# MCU.net
KiCad netlist of a schematic drawn in Altium Designer
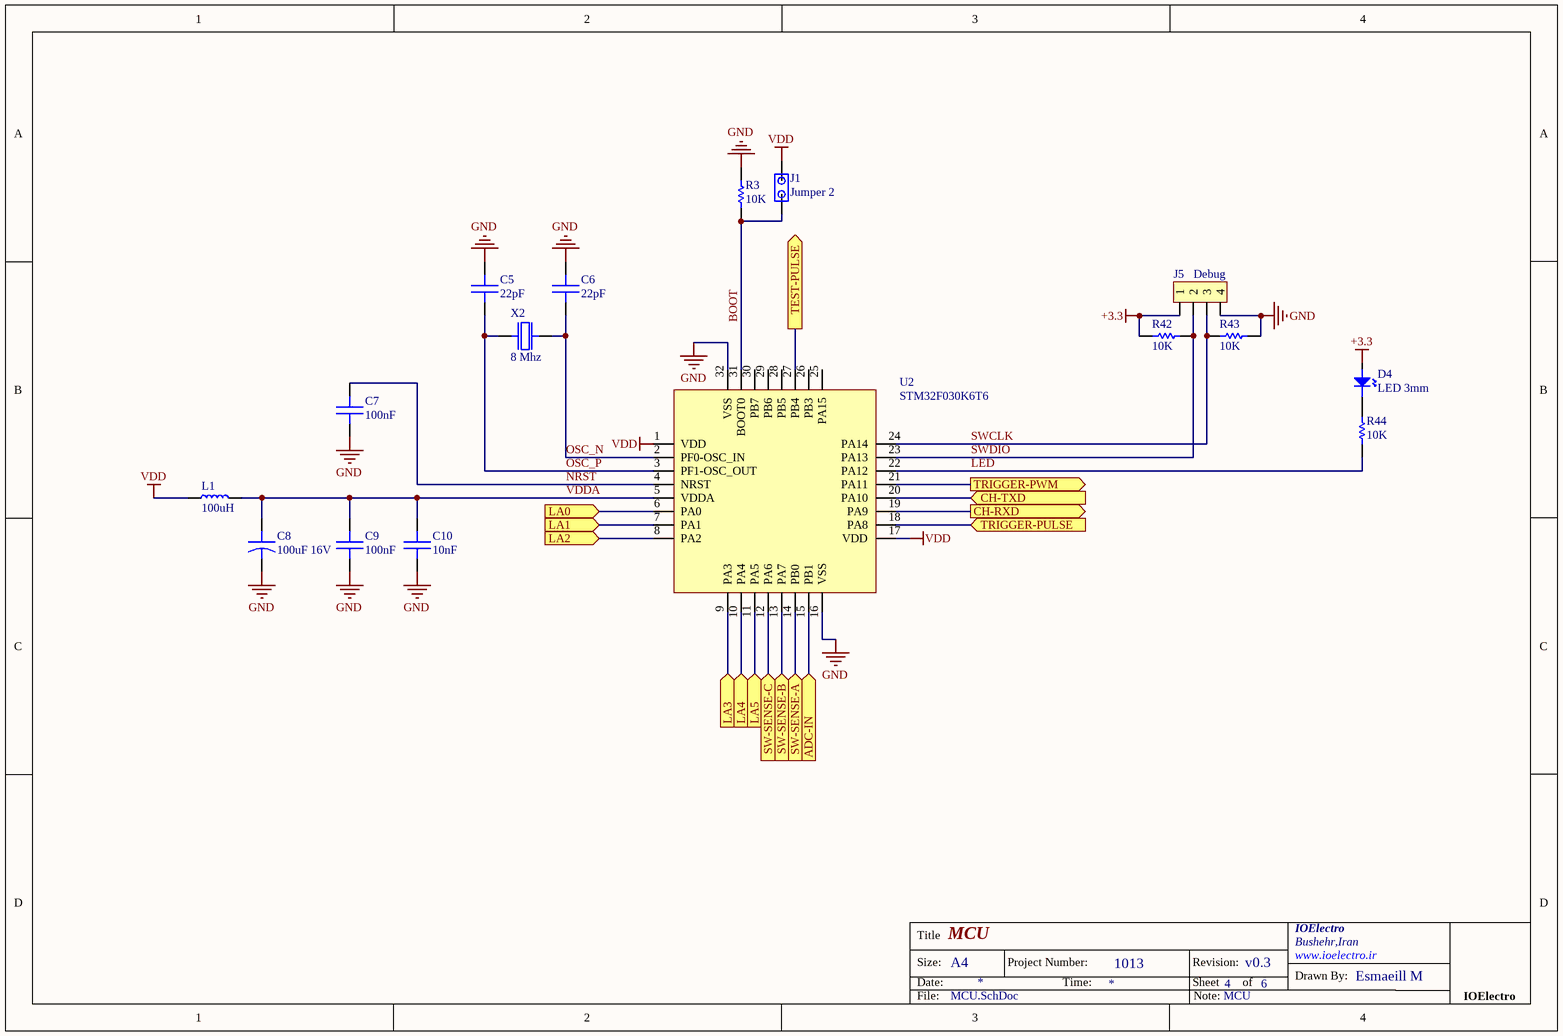
[diagram p0: MCU.SchDoc]

(export (version "E")
  (design (tool "Eeschema 10.0.6"))
  (components
    (comp (ref "C5")
      (value "22pF")
      (footprint "C-0805")
      (description "SMD 0805")
      (libsource (lib "IOElectro") (part "CAP"))
    )
    (comp (ref "C6")
      (value "22pF")
      (footprint "C-0805")
      (description "SMD 0805")
      (libsource (lib "IOElectro") (part "CAP"))
    )
    (comp (ref "C7")
      (value "100nF")
      (footprint "C-0805")
      (description "SMD 0805")
      (libsource (lib "IOElectro") (part "CAP"))
    )
    (comp (ref "C8")
      (value "100uF 16V")
      (footprint "C-EL_6.5x7x2.5mm")
      (description "CAPACITOR ELECTROLYTIC 6.3x7mm")
      (libsource (lib "IOElectro") (part "CAP-EL"))
    )
    (comp (ref "C9")
      (value "100nF")
      (footprint "C-0805")
      (description "SMD 0805")
      (libsource (lib "IOElectro") (part "CAP"))
    )
    (comp (ref "C10")
      (value "10nF")
      (footprint "C-0805")
      (description "SMD 0805")
      (libsource (lib "IOElectro") (part "CAP"))
    )
    (comp (ref "D4")
      (value "LED 3mm")
      (footprint "LED-3MM")
      (description "LED")
      (libsource (lib "IOElectro") (part "LED"))
    )
    (comp (ref "J1")
      (value "Jumper 2")
      (footprint "JAMPER-2-DIP_2.56mm")
      (description "2PIN DIP JAMPER 2.56mm")
      (libsource (lib "IOElectro") (part "JUMPER-2"))
    )
    (comp (ref "J5")
      (value "Debug")
      (footprint "PH-1X4")
      (description "PIN HEADER 1x4 2.56mm")
      (libsource (lib "Schlib") (part "PH-1X4"))
    )
    (comp (ref "L1")
      (value "100uH")
      (footprint "L-DIP_3x7mm_pin9mm")
      (description "Axial Lead Inductors(Coils)For Signal Line 100uH 165mA")
      (libsource (lib "IOElectro") (part "AL0307-101K-LF"))
    )
    (comp (ref "R3")
      (value "10K")
      (footprint "R-0805")
      (description "0805")
      (libsource (lib "IOElectro") (part "RES"))
    )
    (comp (ref "R42")
      (value "10K")
      (footprint "R-0805")
      (description "0805")
      (libsource (lib "IOElectro") (part "RES"))
    )
    (comp (ref "R43")
      (value "10K")
      (footprint "R-0805")
      (description "0805")
      (libsource (lib "IOElectro") (part "RES"))
    )
    (comp (ref "R44")
      (value "10K")
      (footprint "R-0805")
      (description "0805")
      (libsource (lib "IOElectro") (part "RES"))
    )
    (comp (ref "U2")
      (value "STM32F030K6T6")
      (footprint "LQFP-32")
      (fields (field (name "MANUFACTURER") "STMicroelectronics"))
      (libsource (lib "IOElectro") (part "STM32F030K6T6"))
    )
    (comp (ref "X2")
      (value "8 Mhz")
      (footprint "XTAL-DIP_Small")
      (description "Crystal oscillator")
      (libsource (lib "IOElectro") (part "XTAL"))
    )
  )
  (nets
    (net (code "1") (name "+3.3") (class "Default")
      (node (ref "D4") (pin "A") (pinfunction "A_A") (pintype "passive"))
      (node (ref "J5") (pin "1") (pinfunction "1_1") (pintype "passive"))
      (node (ref "R42") (pin "1") (pinfunction "1_1") (pintype "passive"))
    )
    (net (code "3") (name "/ADC-IN") (class "Default")
      (node (ref "U2") (pin "15") (pinfunction "PB1_15") (pintype "passive"))
    )
    (net (code "4") (name "/BOOT") (class "Default")
      (node (ref "J1") (pin "1") (pinfunction "1_1") (pintype "passive"))
      (node (ref "R3") (pin "1") (pinfunction "1_1") (pintype "passive"))
      (node (ref "U2") (pin "31") (pinfunction "BOOT0_31") (pintype "passive"))
    )
    (net (code "5") (name "/CH-RXD") (class "Default")
      (node (ref "U2") (pin "19") (pinfunction "PA9_19") (pintype "passive"))
    )
    (net (code "6") (name "/CH-TXD") (class "Default")
      (node (ref "U2") (pin "20") (pinfunction "PA10_20") (pintype "passive"))
    )
    (net (code "7") (name "/LA0") (class "Default")
      (node (ref "U2") (pin "6") (pinfunction "PA0_6") (pintype "passive"))
    )
    (net (code "8") (name "/LA1") (class "Default")
      (node (ref "U2") (pin "7") (pinfunction "PA1_7") (pintype "passive"))
    )
    (net (code "9") (name "/LA2") (class "Default")
      (node (ref "U2") (pin "8") (pinfunction "PA2_8") (pintype "passive"))
    )
    (net (code "10") (name "/LA3") (class "Default")
      (node (ref "U2") (pin "9") (pinfunction "PA3_9") (pintype "passive"))
    )
    (net (code "11") (name "/LA4") (class "Default")
      (node (ref "U2") (pin "10") (pinfunction "PA4_10") (pintype "passive"))
    )
    (net (code "12") (name "/LA5") (class "Default")
      (node (ref "U2") (pin "11") (pinfunction "PA5_11") (pintype "passive"))
    )
    (net (code "13") (name "/LED") (class "Default")
      (node (ref "R44") (pin "2") (pinfunction "2_2") (pintype "passive"))
      (node (ref "U2") (pin "22") (pinfunction "PA12_22") (pintype "passive"))
    )
    (net (code "14") (name "/NRST") (class "Default")
      (node (ref "C7") (pin "1") (pinfunction "1_1") (pintype "passive"))
      (node (ref "U2") (pin "4") (pinfunction "NRST_4") (pintype "passive"))
    )
    (net (code "15") (name "/OSC_N") (class "Default")
      (node (ref "C6") (pin "1") (pinfunction "1_1") (pintype "passive"))
      (node (ref "U2") (pin "2") (pinfunction "PF0-OSC_IN_2") (pintype "passive"))
      (node (ref "X2") (pin "2") (pinfunction "2_2") (pintype "passive"))
    )
    (net (code "16") (name "/OSC_P") (class "Default")
      (node (ref "C5") (pin "1") (pinfunction "1_1") (pintype "passive"))
      (node (ref "U2") (pin "3") (pinfunction "PF1-OSC_OUT_3") (pintype "passive"))
      (node (ref "X2") (pin "1") (pinfunction "1_1") (pintype "passive"))
    )
    (net (code "17") (name "/SW-SENSE-A") (class "Default")
      (node (ref "U2") (pin "14") (pinfunction "PB0_14") (pintype "passive"))
    )
    (net (code "18") (name "/SW-SENSE-B") (class "Default")
      (node (ref "U2") (pin "13") (pinfunction "PA7_13") (pintype "passive"))
    )
    (net (code "19") (name "/SW-SENSE-C") (class "Default")
      (node (ref "U2") (pin "12") (pinfunction "PA6_12") (pintype "passive"))
    )
    (net (code "20") (name "/SWCLK") (class "Default")
      (node (ref "J5") (pin "3") (pinfunction "3_3") (pintype "passive"))
      (node (ref "R43") (pin "1") (pinfunction "1_1") (pintype "passive"))
      (node (ref "U2") (pin "24") (pinfunction "PA14_24") (pintype "passive"))
    )
    (net (code "21") (name "/SWDIO") (class "Default")
      (node (ref "J5") (pin "2") (pinfunction "2_2") (pintype "passive"))
      (node (ref "R42") (pin "2") (pinfunction "2_2") (pintype "passive"))
      (node (ref "U2") (pin "23") (pinfunction "PA13_23") (pintype "passive"))
    )
    (net (code "22") (name "/TEST-PULSE") (class "Default")
      (node (ref "U2") (pin "27") (pinfunction "PB4_27") (pintype "passive"))
    )
    (net (code "23") (name "/TRIGGER-PULSE") (class "Default")
      (node (ref "U2") (pin "18") (pinfunction "PA8_18") (pintype "passive"))
    )
    (net (code "24") (name "/TRIGGER-PWM") (class "Default")
      (node (ref "U2") (pin "21") (pinfunction "PA11_21") (pintype "passive"))
    )
    (net (code "25") (name "/VDDA") (class "Default")
      (node (ref "C10") (pin "1") (pinfunction "1_1") (pintype "passive"))
      (node (ref "C8") (pin "A") (pinfunction "A_A") (pintype "passive"))
      (node (ref "C9") (pin "1") (pinfunction "1_1") (pintype "passive"))
      (node (ref "L1") (pin "2") (pinfunction "2_2") (pintype "passive"))
      (node (ref "U2") (pin "5") (pinfunction "VDDA_5") (pintype "passive"))
    )
    (net (code "26") (name "GND") (class "Default")
      (node (ref "C10") (pin "2") (pinfunction "2_2") (pintype "passive"))
      (node (ref "C5") (pin "2") (pinfunction "2_2") (pintype "passive"))
      (node (ref "C6") (pin "2") (pinfunction "2_2") (pintype "passive"))
      (node (ref "C7") (pin "2") (pinfunction "2_2") (pintype "passive"))
      (node (ref "C8") (pin "K") (pinfunction "K_K") (pintype "passive"))
      (node (ref "C9") (pin "2") (pinfunction "2_2") (pintype "passive"))
      (node (ref "J5") (pin "4") (pinfunction "4_4") (pintype "passive"))
      (node (ref "R3") (pin "2") (pinfunction "2_2") (pintype "passive"))
      (node (ref "R43") (pin "2") (pinfunction "2_2") (pintype "passive"))
      (node (ref "U2") (pin "16") (pinfunction "VSS_16") (pintype "passive"))
      (node (ref "U2") (pin "32") (pinfunction "VSS_32") (pintype "passive"))
    )
    (net (code "27") (name "Net-(D4-PadK)") (class "Default")
      (node (ref "D4") (pin "K") (pinfunction "K_K") (pintype "passive"))
      (node (ref "R44") (pin "1") (pinfunction "1_1") (pintype "passive"))
    )
    (net (code "28") (name "VDD") (class "Default")
      (node (ref "J1") (pin "2") (pinfunction "2_2") (pintype "passive"))
      (node (ref "L1") (pin "1") (pinfunction "1_1") (pintype "passive"))
      (node (ref "U2") (pin "1") (pinfunction "VDD_1") (pintype "passive"))
      (node (ref "U2") (pin "17") (pinfunction "VDD_17") (pintype "passive"))
    )
    (net (code "29") (name "unconnected-(U2-PA15-Pad25)") (class "Default")
      (node (ref "U2") (pin "25") (pinfunction "PA15_25") (pintype "passive"))
    )
    (net (code "30") (name "unconnected-(U2-PB3-Pad26)") (class "Default")
      (node (ref "U2") (pin "26") (pinfunction "PB3_26") (pintype "passive"))
    )
    (net (code "31") (name "unconnected-(U2-PB5-Pad28)") (class "Default")
      (node (ref "U2") (pin "28") (pinfunction "PB5_28") (pintype "passive"))
    )
    (net (code "32") (name "unconnected-(U2-PB6-Pad29)") (class "Default")
      (node (ref "U2") (pin "29") (pinfunction "PB6_29") (pintype "passive"))
    )
    (net (code "33") (name "unconnected-(U2-PB7-Pad30)") (class "Default")
      (node (ref "U2") (pin "30") (pinfunction "PB7_30") (pintype "passive"))
    )
  )
)
